# SIM800.net
KiCad netlist of a schematic drawn in Altium Designer
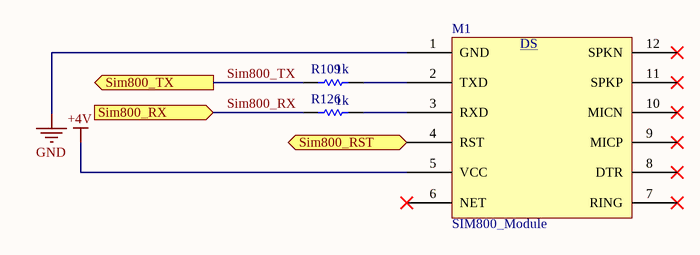
[diagram p0: SIM800.SchDoc]

(export (version "E")
  (design (tool "Eeschema 10.0.6"))
  (components
    (comp (ref "M1")
      (value "SIM800_Module")
      (footprint "SIM800_Module")
      (libsource (lib "AfraLIB") (part "SIM800_Module"))
    )
    (comp (ref "R109")
      (value "1k")
      (footprint "R-805")
      (description "Resistor")
      (fields (field (name "Comment") "R-805"))
      (libsource (lib "AfraLIB") (part "R-805"))
    )
    (comp (ref "R126")
      (value "1k")
      (footprint "R-805")
      (description "Resistor")
      (fields (field (name "Comment") "R-805"))
      (libsource (lib "AfraLIB") (part "R-805"))
    )
  )
  (nets
    (net (code "1") (name "+4V") (class "Default")
      (node (ref "M1") (pin "5") (pinfunction "VCC_5") (pintype "passive"))
    )
    (net (code "2") (name "/Sim800_RST") (class "Default")
      (node (ref "M1") (pin "4") (pinfunction "RST_4") (pintype "passive"))
    )
    (net (code "3") (name "/Sim800_RX") (class "Default")
      (node (ref "R126") (pin "2") (pinfunction "2_2") (pintype "passive"))
    )
    (net (code "4") (name "/Sim800_TX") (class "Default")
      (node (ref "R109") (pin "2") (pinfunction "2_2") (pintype "passive"))
    )
    (net (code "5") (name "GND") (class "Default")
      (node (ref "M1") (pin "1") (pinfunction "GND_1") (pintype "passive"))
    )
    (net (code "6") (name "Net-(M1-RXD)") (class "Default")
      (node (ref "M1") (pin "3") (pinfunction "RXD_3") (pintype "passive"))
      (node (ref "R126") (pin "1") (pinfunction "1_1") (pintype "passive"))
    )
    (net (code "7") (name "Net-(M1-TXD)") (class "Default")
      (node (ref "M1") (pin "2") (pinfunction "TXD_2") (pintype "passive"))
      (node (ref "R109") (pin "1") (pinfunction "1_1") (pintype "passive"))
    )
    (net (code "8") (name "unconnected-(M1-DTR-Pad8)") (class "Default")
      (node (ref "M1") (pin "8") (pinfunction "DTR_8") (pintype "passive+no_connect"))
    )
    (net (code "9") (name "unconnected-(M1-MICN-Pad10)") (class "Default")
      (node (ref "M1") (pin "10") (pinfunction "MICN_10") (pintype "passive+no_connect"))
    )
    (net (code "10") (name "unconnected-(M1-MICP-Pad9)") (class "Default")
      (node (ref "M1") (pin "9") (pinfunction "MICP_9") (pintype "passive+no_connect"))
    )
    (net (code "11") (name "unconnected-(M1-NET-Pad6)") (class "Default")
      (node (ref "M1") (pin "6") (pinfunction "NET_6") (pintype "passive+no_connect"))
    )
    (net (code "12") (name "unconnected-(M1-RING-Pad7)") (class "Default")
      (node (ref "M1") (pin "7") (pinfunction "RING_7") (pintype "passive+no_connect"))
    )
    (net (code "13") (name "unconnected-(M1-SPKN-Pad12)") (class "Default")
      (node (ref "M1") (pin "12") (pinfunction "SPKN_12") (pintype "passive+no_connect"))
    )
    (net (code "14") (name "unconnected-(M1-SPKP-Pad11)") (class "Default")
      (node (ref "M1") (pin "11") (pinfunction "SPKP_11") (pintype "passive+no_connect"))
    )
  )
)
